# FaultDet.net
KiCad netlist of a schematic drawn in Altium Designer
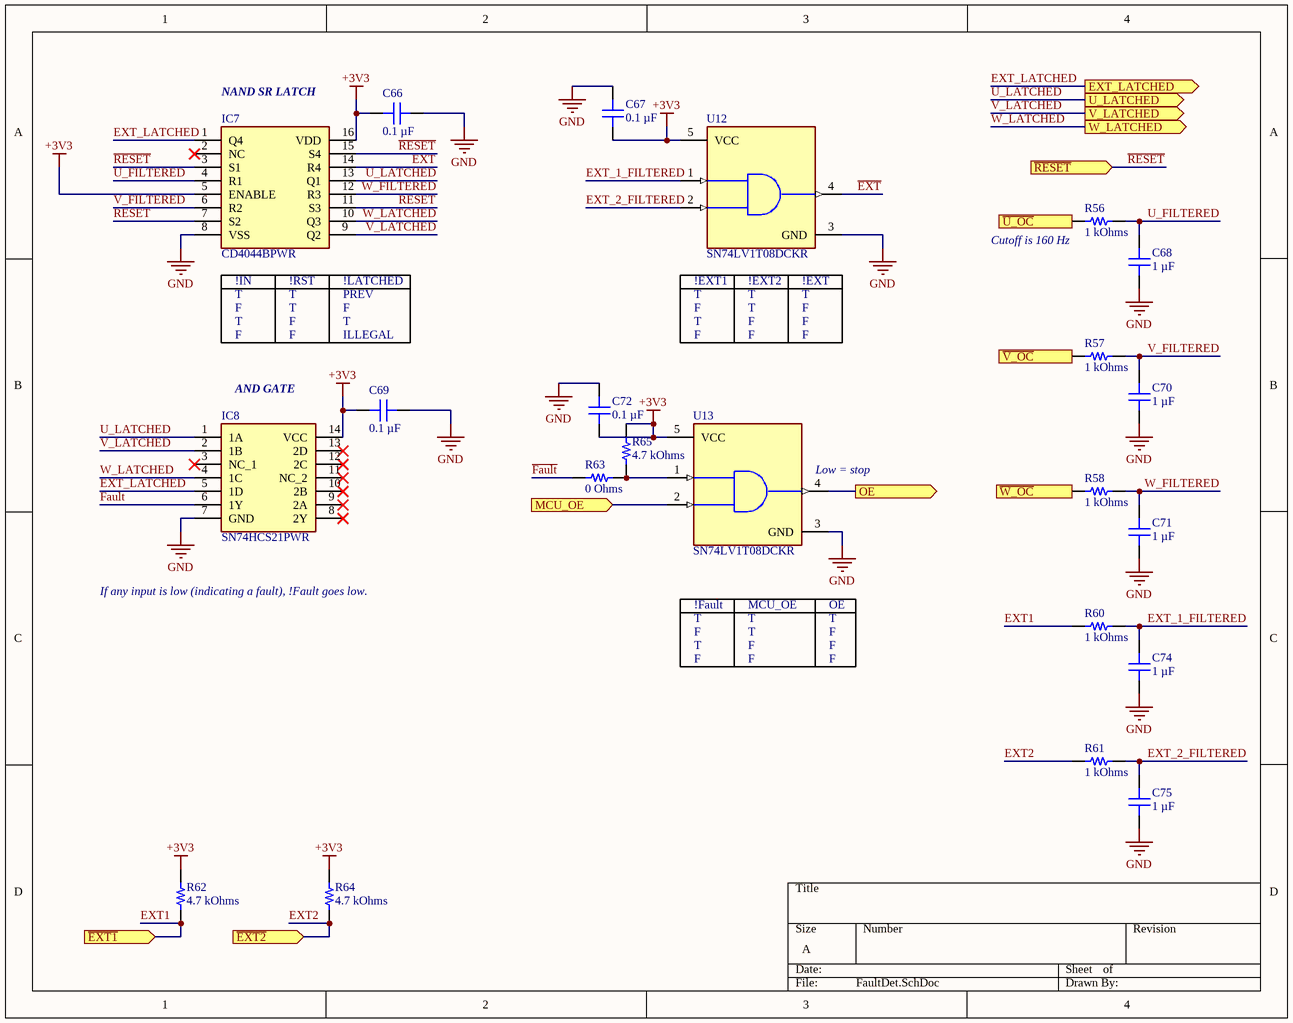
[diagram p0: FaultDet.SchDoc]

(export (version "E")
  (design (tool "Eeschema 10.0.6"))
  (components
    (comp (ref "C66")
      (value "0.1 µF")
      (footprint "CAP 0402_1005")
      (description "CAP CER 0402 0.1UF 16V X7R 10%")
      (fields
        (field (name "PART NUMBER") "C0402C104K4RECAUTO")
        (field (name "CAPACITANCE") "0.1 µF")
        (field (name "MANUFACTURER") "KEMET")
      )
      (libsource (lib "Celestial Altium Library - altium_library") (part "Capacitor"))
    )
    (comp (ref "C67")
      (value "0.1 µF")
      (footprint "CAP 0402_1005")
      (description "CAP CER 0402 0.1UF 16V X7R 10%")
      (fields
        (field (name "PART NUMBER") "C0402C104K4RECAUTO")
        (field (name "CAPACITANCE") "0.1 µF")
        (field (name "MANUFACTURER") "KEMET")
      )
      (libsource (lib "Celestial Altium Library - altium_library") (part "Capacitor"))
    )
    (comp (ref "C68")
      (value "1 µF")
      (footprint "MURATA GRM155 0402_1005")
      (description "CAP CER 1UF 10V X7S 0402")
      (fields
        (field (name "PART NUMBER") "GRM155C71A105KE11D")
        (field (name "CAPACITANCE") "1 µF")
        (field (name "MANUFACTURER") "Murata Electronics")
      )
      (libsource (lib "Celestial Altium Library - altium_library") (part "Capacitor"))
    )
    (comp (ref "C69")
      (value "0.1 µF")
      (footprint "CAP 0402_1005")
      (description "CAP CER 0402 0.1UF 16V X7R 10%")
      (fields
        (field (name "PART NUMBER") "C0402C104K4RECAUTO")
        (field (name "CAPACITANCE") "0.1 µF")
        (field (name "MANUFACTURER") "KEMET")
      )
      (libsource (lib "Celestial Altium Library - altium_library") (part "Capacitor"))
    )
    (comp (ref "C70")
      (value "1 µF")
      (footprint "MURATA GRM155 0402_1005")
      (description "CAP CER 1UF 10V X7S 0402")
      (fields
        (field (name "PART NUMBER") "GRM155C71A105KE11D")
        (field (name "CAPACITANCE") "1 µF")
        (field (name "MANUFACTURER") "Murata Electronics")
      )
      (libsource (lib "Celestial Altium Library - altium_library") (part "Capacitor"))
    )
    (comp (ref "C71")
      (value "1 µF")
      (footprint "MURATA GRM155 0402_1005")
      (description "CAP CER 1UF 10V X7S 0402")
      (fields
        (field (name "PART NUMBER") "GRM155C71A105KE11D")
        (field (name "CAPACITANCE") "1 µF")
        (field (name "MANUFACTURER") "Murata Electronics")
      )
      (libsource (lib "Celestial Altium Library - altium_library") (part "Capacitor"))
    )
    (comp (ref "C72")
      (value "0.1 µF")
      (footprint "CAP 0402_1005")
      (description "CAP CER 0402 0.1UF 16V X7R 10%")
      (fields
        (field (name "PART NUMBER") "C0402C104K4RECAUTO")
        (field (name "CAPACITANCE") "0.1 µF")
        (field (name "MANUFACTURER") "KEMET")
      )
      (libsource (lib "Celestial Altium Library - altium_library") (part "Capacitor"))
    )
    (comp (ref "C74")
      (value "1 µF")
      (footprint "MURATA GRM155 0402_1005")
      (description "CAP CER 1UF 10V X7S 0402")
      (fields
        (field (name "PART NUMBER") "GRM155C71A105KE11D")
        (field (name "CAPACITANCE") "1 µF")
        (field (name "MANUFACTURER") "Murata Electronics")
      )
      (libsource (lib "Celestial Altium Library - altium_library") (part "Capacitor"))
    )
    (comp (ref "C75")
      (value "1 µF")
      (footprint "MURATA GRM155 0402_1005")
      (description "CAP CER 1UF 10V X7S 0402")
      (fields
        (field (name "PART NUMBER") "GRM155C71A105KE11D")
        (field (name "CAPACITANCE") "1 µF")
        (field (name "MANUFACTURER") "Murata Electronics")
      )
      (libsource (lib "Celestial Altium Library - altium_library") (part "Capacitor"))
    )
    (comp (ref "IC7")
      (value "CD4044BPWR")
      (footprint "PcbLib1:SOP65P640X120-16N")
      (description "Integrated Circuit")
      (fields (field (name "MOUSER PART NUMBER") "595-CD4044BPWR"))
      (libsource (lib "*") (part "CD4044BPWR"))
    )
    (comp (ref "IC8")
      (value "SN74HCS21PWR")
      (footprint "PcbLib1:SOP65P640X120-14N")
      (description "Integrated Circuit")
      (fields (field (name "MOUSER PART NUMBER") "595-SN74HCS21PWR"))
      (libsource (lib "*") (part "SN74HCS21PWR"))
    )
    (comp (ref "R56")
      (value "1 kOhms")
      (footprint "YAGEO RES 0402_1005")
      (description "RES SMD 1K OHM 0.1% 1/16W 0402")
      (fields (field (name "PART NUMBER") "AT0402BRD071KL") (field (name "MANUFACTURER") "Yageo"))
      (libsource (lib "Celestial Altium Library - altium_library") (part "Resistor"))
    )
    (comp (ref "R57")
      (value "1 kOhms")
      (footprint "YAGEO RES 0402_1005")
      (description "RES SMD 1K OHM 0.1% 1/16W 0402")
      (fields (field (name "PART NUMBER") "AT0402BRD071KL") (field (name "MANUFACTURER") "Yageo"))
      (libsource (lib "Celestial Altium Library - altium_library") (part "Resistor"))
    )
    (comp (ref "R58")
      (value "1 kOhms")
      (footprint "YAGEO RES 0402_1005")
      (description "RES SMD 1K OHM 0.1% 1/16W 0402")
      (fields (field (name "PART NUMBER") "AT0402BRD071KL") (field (name "MANUFACTURER") "Yageo"))
      (libsource (lib "Celestial Altium Library - altium_library") (part "Resistor"))
    )
    (comp (ref "R60")
      (value "1 kOhms")
      (footprint "YAGEO RES 0402_1005")
      (description "RES SMD 1K OHM 0.1% 1/16W 0402")
      (fields (field (name "PART NUMBER") "AT0402BRD071KL") (field (name "MANUFACTURER") "Yageo"))
      (libsource (lib "Celestial Altium Library - altium_library") (part "Resistor"))
    )
    (comp (ref "R61")
      (value "1 kOhms")
      (footprint "YAGEO RES 0402_1005")
      (description "RES SMD 1K OHM 0.1% 1/16W 0402")
      (fields (field (name "PART NUMBER") "AT0402BRD071KL") (field (name "MANUFACTURER") "Yageo"))
      (libsource (lib "Celestial Altium Library - altium_library") (part "Resistor"))
    )
    (comp (ref "R62")
      (value "4.7 kOhms")
      (footprint "YAGEO RES 0402_1005")
      (description "RES SMD 4.7K OHM 1% 1/16W 0402")
      (fields (field (name "PART NUMBER") "RT0402FRE074K7L") (field (name "MANUFACTURER") "Yageo"))
      (libsource (lib "Celestial Altium Library - altium_library") (part "Resistor"))
    )
    (comp (ref "R63")
      (value "0 Ohms")
      (footprint "RES 0402_1005")
      (description "0402 JUMPER ON TAPE AND REEL")
      (fields (field (name "PART NUMBER") "5112") (field (name "MANUFACTURER") "Keystone Electronics"))
      (libsource (lib "Celestial Altium Library - altium_library") (part "Resistor"))
    )
    (comp (ref "R64")
      (value "4.7 kOhms")
      (footprint "YAGEO RES 0402_1005")
      (description "RES SMD 4.7K OHM 1% 1/16W 0402")
      (fields (field (name "PART NUMBER") "RT0402FRE074K7L") (field (name "MANUFACTURER") "Yageo"))
      (libsource (lib "Celestial Altium Library - altium_library") (part "Resistor"))
    )
    (comp (ref "R65")
      (value "4.7 kOhms")
      (footprint "YAGEO RES 0402_1005")
      (description "RES SMD 4.7K OHM 1% 1/16W 0402")
      (fields (field (name "PART NUMBER") "RT0402FRE074K7L") (field (name "MANUFACTURER") "Yageo"))
      (libsource (lib "Celestial Altium Library - altium_library") (part "Resistor"))
    )
    (comp (ref "U12")
      (value "SN74LV1T08DCKR")
      (footprint "FP-DCK0005A-IPC_C")
      (description "IC GATE AND 1CH 2-INP SC70-5")
      (libsource (lib "Altium Content Vault") (part "7c18de2f9dfcb298a2c7fe949342ca2"))
    )
    (comp (ref "U13")
      (value "SN74LV1T08DCKR")
      (footprint "FP-DCK0005A-IPC_C")
      (description "IC GATE AND 1CH 2-INP SC70-5")
      (libsource (lib "Altium Content Vault") (part "7c18de2f9dfcb298a2c7fe949342ca2"))
    )
  )
  (nets
    (net (code "1") (name "+3V3") (class "Default")
      (node (ref "C66") (pin "2") (pinfunction "2_2") (pintype "passive"))
      (node (ref "C67") (pin "1") (pinfunction "1_1") (pintype "passive"))
      (node (ref "C69") (pin "2") (pinfunction "2_2") (pintype "passive"))
      (node (ref "C72") (pin "1") (pinfunction "1_1") (pintype "passive"))
      (node (ref "IC7") (pin "16") (pinfunction "VDD_16") (pintype "passive"))
      (node (ref "IC7") (pin "5") (pinfunction "ENABLE_5") (pintype "passive"))
      (node (ref "IC8") (pin "14") (pinfunction "VCC_14") (pintype "passive"))
      (node (ref "R62") (pin "2") (pinfunction "2_2") (pintype "passive"))
      (node (ref "R64") (pin "2") (pinfunction "2_2") (pintype "passive"))
      (node (ref "R65") (pin "2") (pinfunction "2_2") (pintype "passive"))
      (node (ref "U12") (pin "5") (pinfunction "VCC_5") (pintype "power_in"))
      (node (ref "U13") (pin "5") (pinfunction "VCC_5") (pintype "power_in"))
    )
    (net (code "2") (name "/EXT1") (class "Default")
      (node (ref "R60") (pin "1") (pinfunction "1_1") (pintype "passive"))
      (node (ref "R62") (pin "1") (pinfunction "1_1") (pintype "passive"))
    )
    (net (code "3") (name "/EXT2") (class "Default")
      (node (ref "R61") (pin "1") (pinfunction "1_1") (pintype "passive"))
      (node (ref "R64") (pin "1") (pinfunction "1_1") (pintype "passive"))
    )
    (net (code "4") (name "/EXT_1_FILTERED") (class "Default")
      (node (ref "C74") (pin "2") (pinfunction "2_2") (pintype "passive"))
      (node (ref "R60") (pin "2") (pinfunction "2_2") (pintype "passive"))
      (node (ref "U12") (pin "1") (pinfunction "A_1") (pintype "input"))
    )
    (net (code "5") (name "/EXT_2_FILTERED") (class "Default")
      (node (ref "C75") (pin "2") (pinfunction "2_2") (pintype "passive"))
      (node (ref "R61") (pin "2") (pinfunction "2_2") (pintype "passive"))
      (node (ref "U12") (pin "2") (pinfunction "B_2") (pintype "input"))
    )
    (net (code "6") (name "/EXT_LATCHED") (class "Default")
      (node (ref "IC7") (pin "1") (pinfunction "Q4_1") (pintype "passive"))
      (node (ref "IC8") (pin "5") (pinfunction "1D_5") (pintype "passive"))
    )
    (net (code "7") (name "/MCU_OE") (class "Default")
      (node (ref "U13") (pin "2") (pinfunction "B_2") (pintype "input"))
    )
    (net (code "8") (name "/OE") (class "Default")
      (node (ref "U13") (pin "4") (pinfunction "Y_4") (pintype "output"))
    )
    (net (code "9") (name "/U_FILTERED") (class "Default")
      (node (ref "C68") (pin "2") (pinfunction "2_2") (pintype "passive"))
      (node (ref "IC7") (pin "4") (pinfunction "R1_4") (pintype "passive"))
      (node (ref "R56") (pin "2") (pinfunction "2_2") (pintype "passive"))
    )
    (net (code "10") (name "/U_LATCHED") (class "Default")
      (node (ref "IC7") (pin "13") (pinfunction "Q1_13") (pintype "passive"))
      (node (ref "IC8") (pin "1") (pinfunction "1A_1") (pintype "passive"))
    )
    (net (code "11") (name "/V_FILTERED") (class "Default")
      (node (ref "C70") (pin "2") (pinfunction "2_2") (pintype "passive"))
      (node (ref "IC7") (pin "6") (pinfunction "R2_6") (pintype "passive"))
      (node (ref "R57") (pin "2") (pinfunction "2_2") (pintype "passive"))
    )
    (net (code "12") (name "/V_LATCHED") (class "Default")
      (node (ref "IC7") (pin "9") (pinfunction "Q2_9") (pintype "passive"))
      (node (ref "IC8") (pin "2") (pinfunction "1B_2") (pintype "passive"))
    )
    (net (code "13") (name "/W_FILTERED") (class "Default")
      (node (ref "C71") (pin "2") (pinfunction "2_2") (pintype "passive"))
      (node (ref "IC7") (pin "12") (pinfunction "R3_12") (pintype "passive"))
      (node (ref "R58") (pin "2") (pinfunction "2_2") (pintype "passive"))
    )
    (net (code "14") (name "/W_LATCHED") (class "Default")
      (node (ref "IC7") (pin "10") (pinfunction "Q3_10") (pintype "passive"))
      (node (ref "IC8") (pin "4") (pinfunction "1C_4") (pintype "passive"))
    )
    (net (code "15") (name "/~{EXT}") (class "Default")
      (node (ref "IC7") (pin "14") (pinfunction "R4_14") (pintype "passive"))
      (node (ref "U12") (pin "4") (pinfunction "Y_4") (pintype "output"))
    )
    (net (code "16") (name "/~{Fault}") (class "Default")
      (node (ref "IC8") (pin "6") (pinfunction "1Y_6") (pintype "passive"))
      (node (ref "R63") (pin "1") (pinfunction "1_1") (pintype "passive"))
    )
    (net (code "17") (name "/~{RESET}") (class "Default")
      (node (ref "IC7") (pin "11") (pinfunction "S3_11") (pintype "passive"))
      (node (ref "IC7") (pin "15") (pinfunction "S4_15") (pintype "passive"))
      (node (ref "IC7") (pin "3") (pinfunction "S1_3") (pintype "passive"))
      (node (ref "IC7") (pin "7") (pinfunction "S2_7") (pintype "passive"))
    )
    (net (code "18") (name "/~{U_OC}") (class "Default")
      (node (ref "R56") (pin "1") (pinfunction "1_1") (pintype "passive"))
    )
    (net (code "19") (name "/~{V_OC}") (class "Default")
      (node (ref "R57") (pin "1") (pinfunction "1_1") (pintype "passive"))
    )
    (net (code "20") (name "/~{W_OC}") (class "Default")
      (node (ref "R58") (pin "1") (pinfunction "1_1") (pintype "passive"))
    )
    (net (code "21") (name "GND") (class "Default")
      (node (ref "C66") (pin "1") (pinfunction "1_1") (pintype "passive"))
      (node (ref "C67") (pin "2") (pinfunction "2_2") (pintype "passive"))
      (node (ref "C68") (pin "1") (pinfunction "1_1") (pintype "passive"))
      (node (ref "C69") (pin "1") (pinfunction "1_1") (pintype "passive"))
      (node (ref "C70") (pin "1") (pinfunction "1_1") (pintype "passive"))
      (node (ref "C71") (pin "1") (pinfunction "1_1") (pintype "passive"))
      (node (ref "C72") (pin "2") (pinfunction "2_2") (pintype "passive"))
      (node (ref "C74") (pin "1") (pinfunction "1_1") (pintype "passive"))
      (node (ref "C75") (pin "1") (pinfunction "1_1") (pintype "passive"))
      (node (ref "IC7") (pin "8") (pinfunction "VSS_8") (pintype "passive"))
      (node (ref "IC8") (pin "7") (pinfunction "GND_7") (pintype "passive"))
      (node (ref "U12") (pin "3") (pinfunction "GND_3") (pintype "power_in"))
      (node (ref "U13") (pin "3") (pinfunction "GND_3") (pintype "power_in"))
    )
    (net (code "22") (name "Net-(U13-A)") (class "Default")
      (node (ref "R63") (pin "2") (pinfunction "2_2") (pintype "passive"))
      (node (ref "R65") (pin "1") (pinfunction "1_1") (pintype "passive"))
      (node (ref "U13") (pin "1") (pinfunction "A_1") (pintype "input"))
    )
    (net (code "23") (name "unconnected-(IC7-NC-Pad2)") (class "Default")
      (node (ref "IC7") (pin "2") (pinfunction "NC_2") (pintype "passive+no_connect"))
    )
    (net (code "24") (name "unconnected-(IC8-2A-Pad9)") (class "Default")
      (node (ref "IC8") (pin "9") (pinfunction "2A_9") (pintype "passive+no_connect"))
    )
    (net (code "25") (name "unconnected-(IC8-2B-Pad10)") (class "Default")
      (node (ref "IC8") (pin "10") (pinfunction "2B_10") (pintype "passive+no_connect"))
    )
    (net (code "26") (name "unconnected-(IC8-2C-Pad12)") (class "Default")
      (node (ref "IC8") (pin "12") (pinfunction "2C_12") (pintype "passive+no_connect"))
    )
    (net (code "27") (name "unconnected-(IC8-2D-Pad13)") (class "Default")
      (node (ref "IC8") (pin "13") (pinfunction "2D_13") (pintype "passive+no_connect"))
    )
    (net (code "28") (name "unconnected-(IC8-2Y-Pad8)") (class "Default")
      (node (ref "IC8") (pin "8") (pinfunction "2Y_8") (pintype "passive+no_connect"))
    )
    (net (code "29") (name "unconnected-(IC8-NC_1-Pad3)") (class "Default")
      (node (ref "IC8") (pin "3") (pinfunction "NC_1_3") (pintype "passive+no_connect"))
    )
    (net (code "30") (name "unconnected-(IC8-NC_2-Pad11)") (class "Default")
      (node (ref "IC8") (pin "11") (pinfunction "NC_2_11") (pintype "passive+no_connect"))
    )
  )
)
